# USBHUB.net
KiCad netlist of a schematic drawn in Altium Designer
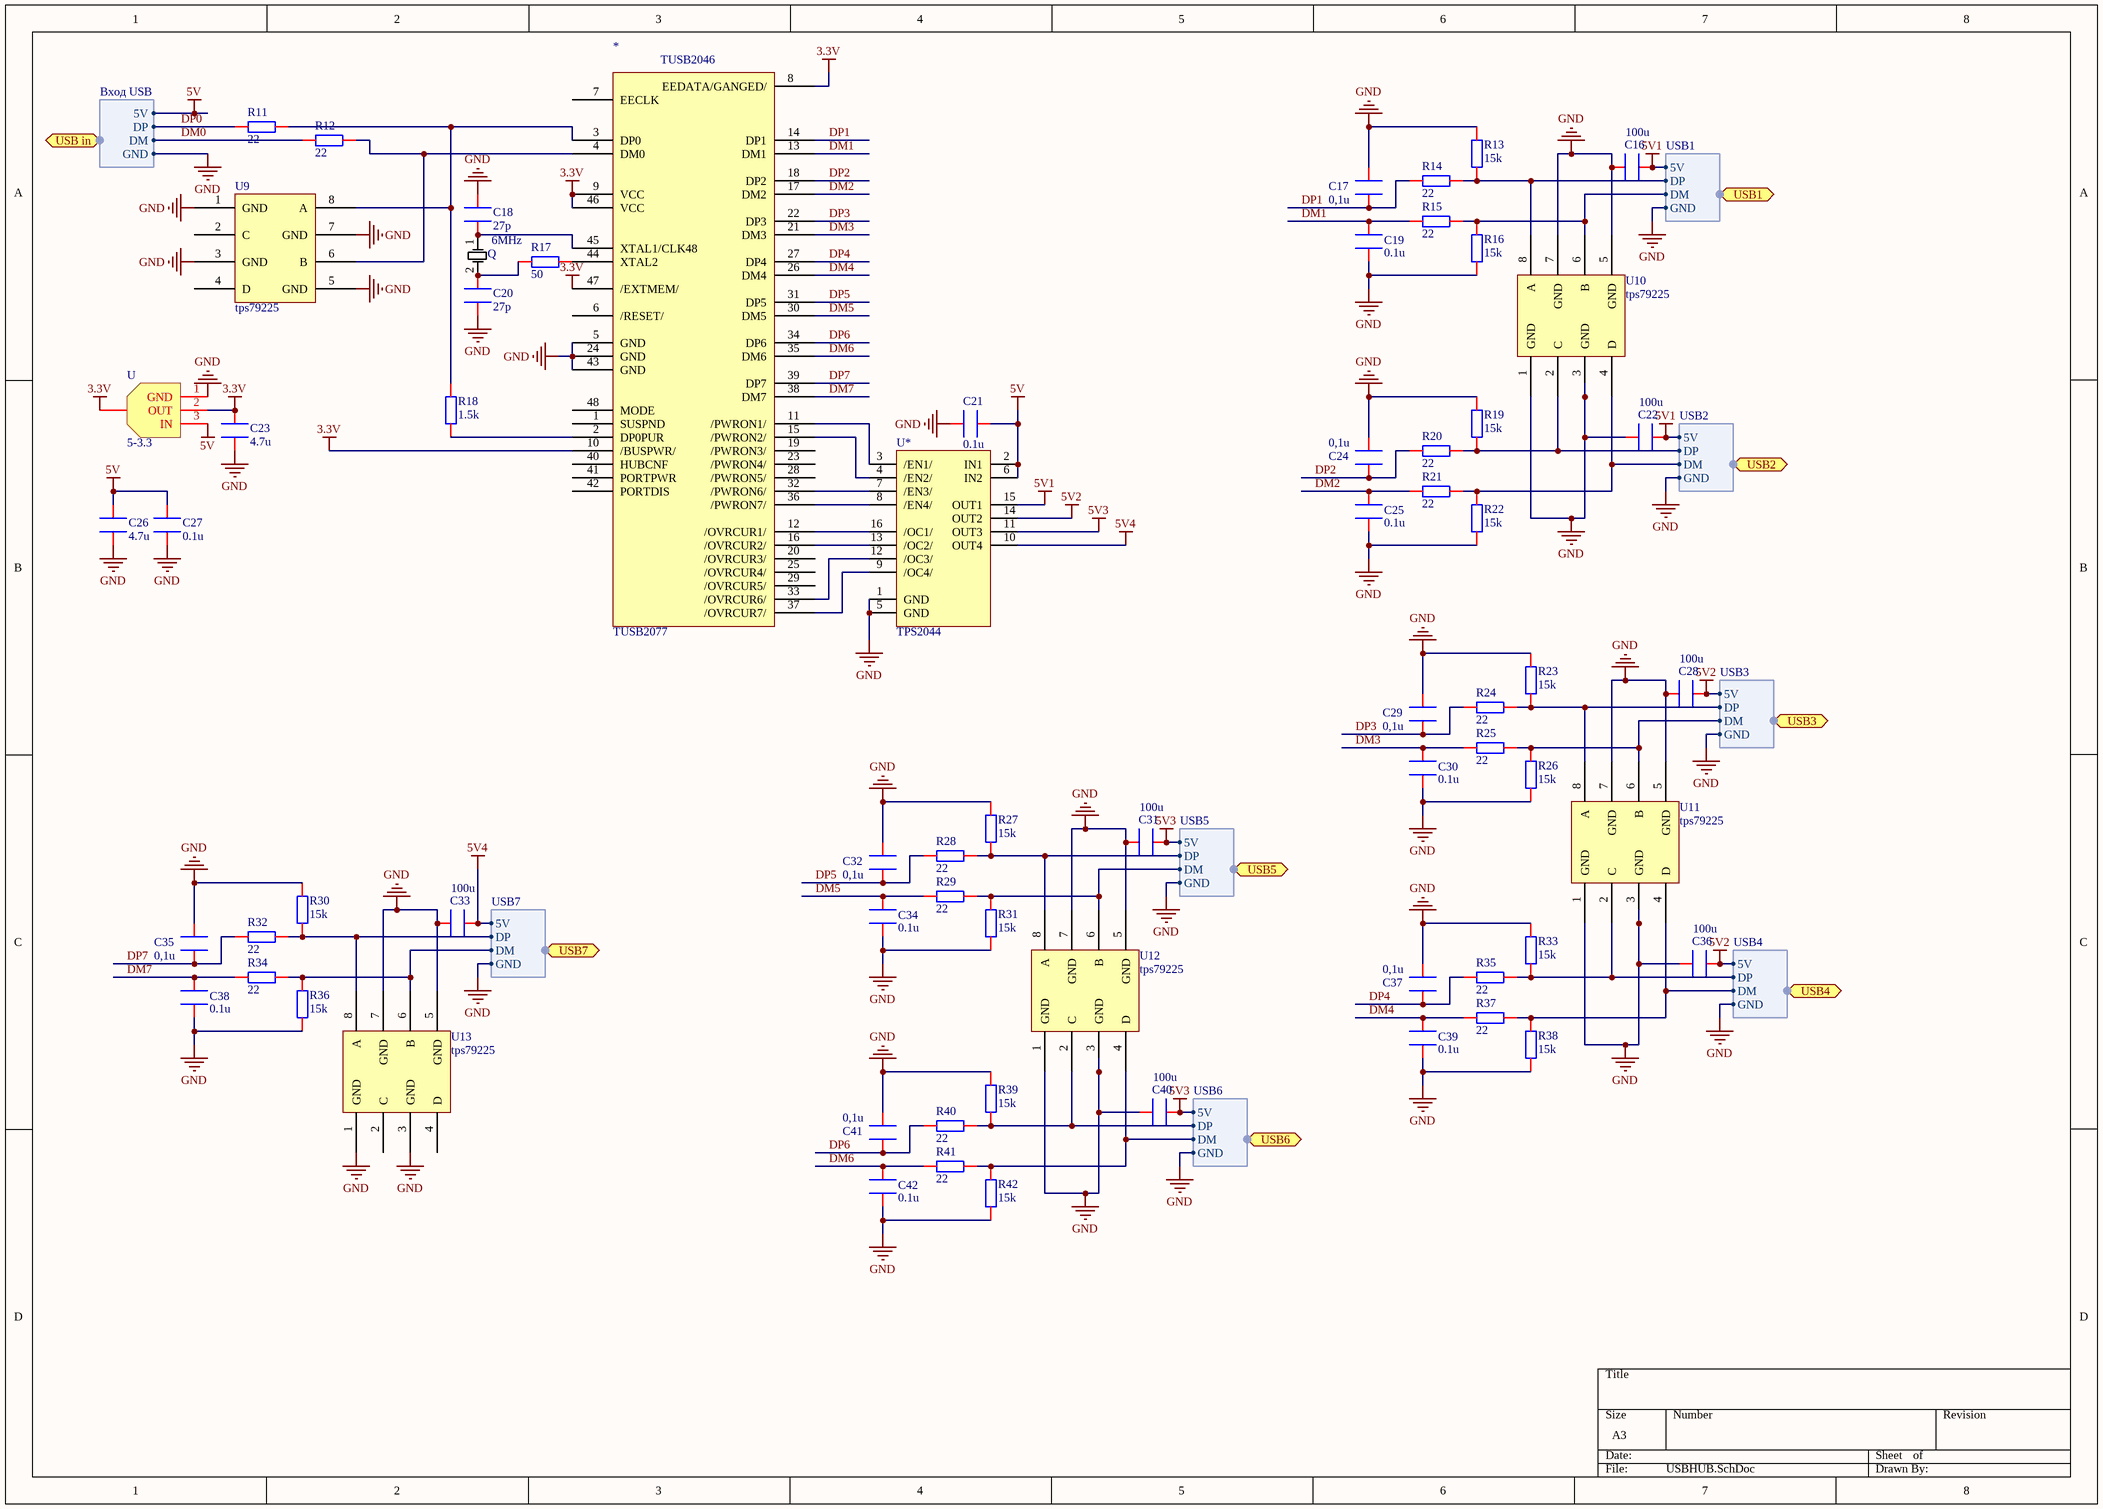
[diagram p0: USBHUB.SchDoc]

(export (version "E")
  (design (tool "Eeschema 10.0.6"))
  (components
    (comp (ref "*") (value "TUSB2077") (libsource (lib "Lib_001") (part "TUSB2077")))
    (comp (ref "C16") (value "100u") (footprint "SMD0603") (libsource (lib "Lib_001") (part "CAP")))
    (comp (ref "C17") (value "0,1u") (footprint "SMD0603") (libsource (lib "Lib_001") (part "CAP")))
    (comp (ref "C18") (value "27p") (footprint "SMD0603") (libsource (lib "Lib_001") (part "CAP")))
    (comp (ref "C19") (value "0.1u") (footprint "SMD0603") (libsource (lib "Lib_001") (part "CAP")))
    (comp (ref "C20") (value "27p") (footprint "SMD0603") (libsource (lib "Lib_001") (part "CAP")))
    (comp (ref "C21") (value "0.1u") (footprint "SMD0603") (libsource (lib "Lib_001") (part "CAP")))
    (comp (ref "C22") (value "100u") (footprint "SMD0603") (libsource (lib "Lib_001") (part "CAP")))
    (comp (ref "C23") (value "4.7u") (footprint "SMD0603") (libsource (lib "Lib_001") (part "CAP")))
    (comp (ref "C24") (value "0,1u") (footprint "SMD0603") (libsource (lib "Lib_001") (part "CAP")))
    (comp (ref "C25") (value "0.1u") (footprint "SMD0603") (libsource (lib "Lib_001") (part "CAP")))
    (comp (ref "C26") (value "4.7u") (footprint "SMD0603") (libsource (lib "Lib_001") (part "CAP")))
    (comp (ref "C27") (value "0.1u") (footprint "SMD0603") (libsource (lib "Lib_001") (part "CAP")))
    (comp (ref "C28") (value "100u") (footprint "SMD0603") (libsource (lib "Lib_001") (part "CAP")))
    (comp (ref "C29") (value "0,1u") (footprint "SMD0603") (libsource (lib "Lib_001") (part "CAP")))
    (comp (ref "C30") (value "0.1u") (footprint "SMD0603") (libsource (lib "Lib_001") (part "CAP")))
    (comp (ref "C31") (value "100u") (footprint "SMD0603") (libsource (lib "Lib_001") (part "CAP")))
    (comp (ref "C32") (value "0,1u") (footprint "SMD0603") (libsource (lib "Lib_001") (part "CAP")))
    (comp (ref "C33") (value "100u") (footprint "SMD0603") (libsource (lib "Lib_001") (part "CAP")))
    (comp (ref "C34") (value "0.1u") (footprint "SMD0603") (libsource (lib "Lib_001") (part "CAP")))
    (comp (ref "C35") (value "0,1u") (footprint "SMD0603") (libsource (lib "Lib_001") (part "CAP")))
    (comp (ref "C36") (value "100u") (footprint "SMD0603") (libsource (lib "Lib_001") (part "CAP")))
    (comp (ref "C37") (value "0,1u") (footprint "SMD0603") (libsource (lib "Lib_001") (part "CAP")))
    (comp (ref "C38") (value "0.1u") (footprint "SMD0603") (libsource (lib "Lib_001") (part "CAP")))
    (comp (ref "C39") (value "0.1u") (footprint "SMD0603") (libsource (lib "Lib_001") (part "CAP")))
    (comp (ref "C40") (value "100u") (footprint "SMD0603") (libsource (lib "Lib_001") (part "CAP")))
    (comp (ref "C41") (value "0,1u") (footprint "SMD0603") (libsource (lib "Lib_001") (part "CAP")))
    (comp (ref "C42") (value "0.1u") (footprint "SMD0603") (libsource (lib "Lib_001") (part "CAP")))
    (comp (ref "Q") (value "6MHz") (libsource (lib "Lib_001") (part "Quartz")))
    (comp (ref "R11") (value "22") (footprint "SMD0805") (libsource (lib "Lib_001") (part "RES_SMD")))
    (comp (ref "R12") (value "22") (footprint "SMD0805") (libsource (lib "Lib_001") (part "RES_SMD")))
    (comp (ref "R13") (value "15k") (footprint "SMD0805") (libsource (lib "Lib_001") (part "RES_SMD")))
    (comp (ref "R14") (value "22") (footprint "SMD0805") (libsource (lib "Lib_001") (part "RES_SMD")))
    (comp (ref "R15") (value "22") (footprint "SMD0805") (libsource (lib "Lib_001") (part "RES_SMD")))
    (comp (ref "R16") (value "15k") (footprint "SMD0805") (libsource (lib "Lib_001") (part "RES_SMD")))
    (comp (ref "R17") (value "50") (footprint "SMD0805") (libsource (lib "Lib_001") (part "RES_SMD")))
    (comp (ref "R18") (value "1.5k") (footprint "SMD0805") (libsource (lib "Lib_001") (part "RES_SMD")))
    (comp (ref "R19") (value "15k") (footprint "SMD0805") (libsource (lib "Lib_001") (part "RES_SMD")))
    (comp (ref "R20") (value "22") (footprint "SMD0805") (libsource (lib "Lib_001") (part "RES_SMD")))
    (comp (ref "R21") (value "22") (footprint "SMD0805") (libsource (lib "Lib_001") (part "RES_SMD")))
    (comp (ref "R22") (value "15k") (footprint "SMD0805") (libsource (lib "Lib_001") (part "RES_SMD")))
    (comp (ref "R23") (value "15k") (footprint "SMD0805") (libsource (lib "Lib_001") (part "RES_SMD")))
    (comp (ref "R24") (value "22") (footprint "SMD0805") (libsource (lib "Lib_001") (part "RES_SMD")))
    (comp (ref "R25") (value "22") (footprint "SMD0805") (libsource (lib "Lib_001") (part "RES_SMD")))
    (comp (ref "R26") (value "15k") (footprint "SMD0805") (libsource (lib "Lib_001") (part "RES_SMD")))
    (comp (ref "R27") (value "15k") (footprint "SMD0805") (libsource (lib "Lib_001") (part "RES_SMD")))
    (comp (ref "R28") (value "22") (footprint "SMD0805") (libsource (lib "Lib_001") (part "RES_SMD")))
    (comp (ref "R29") (value "22") (footprint "SMD0805") (libsource (lib "Lib_001") (part "RES_SMD")))
    (comp (ref "R30") (value "15k") (footprint "SMD0805") (libsource (lib "Lib_001") (part "RES_SMD")))
    (comp (ref "R31") (value "15k") (footprint "SMD0805") (libsource (lib "Lib_001") (part "RES_SMD")))
    (comp (ref "R32") (value "22") (footprint "SMD0805") (libsource (lib "Lib_001") (part "RES_SMD")))
    (comp (ref "R33") (value "15k") (footprint "SMD0805") (libsource (lib "Lib_001") (part "RES_SMD")))
    (comp (ref "R34") (value "22") (footprint "SMD0805") (libsource (lib "Lib_001") (part "RES_SMD")))
    (comp (ref "R35") (value "22") (footprint "SMD0805") (libsource (lib "Lib_001") (part "RES_SMD")))
    (comp (ref "R36") (value "15k") (footprint "SMD0805") (libsource (lib "Lib_001") (part "RES_SMD")))
    (comp (ref "R37") (value "22") (footprint "SMD0805") (libsource (lib "Lib_001") (part "RES_SMD")))
    (comp (ref "R38") (value "15k") (footprint "SMD0805") (libsource (lib "Lib_001") (part "RES_SMD")))
    (comp (ref "R39") (value "15k") (footprint "SMD0805") (libsource (lib "Lib_001") (part "RES_SMD")))
    (comp (ref "R40") (value "22") (footprint "SMD0805") (libsource (lib "Lib_001") (part "RES_SMD")))
    (comp (ref "R41") (value "22") (footprint "SMD0805") (libsource (lib "Lib_001") (part "RES_SMD")))
    (comp (ref "R42") (value "15k") (footprint "SMD0805") (libsource (lib "Lib_001") (part "RES_SMD")))
    (comp (ref "U") (value "5-3.3") (libsource (lib "Lib_001") (part "TLV1117LV")))
    (comp (ref "U*") (value "TPS2044") (footprint "VSSOP-8") (libsource (lib "Lib_001") (part "TPS2044")))
    (comp (ref "U9") (value "tps79225") (footprint "SOT-23-5") (libsource (lib "") (part "SN75240_1")))
    (comp (ref "U10") (value "tps79225") (footprint "SOT-23-5") (libsource (lib "Lib_001") (part "SN75240")))
    (comp (ref "U11") (value "tps79225") (footprint "SOT-23-5") (libsource (lib "Lib_001") (part "SN75240")))
    (comp (ref "U12") (value "tps79225") (footprint "SOT-23-5") (libsource (lib "Lib_001") (part "SN75240")))
    (comp (ref "U13") (value "tps79225") (footprint "SOT-23-5") (libsource (lib "Lib_001") (part "SN75240")))
  )
  (nets
    (net (code "10") (name "/DM0") (class "Default")
      (node (ref "R12") (pin "1") (pinfunction "1_1") (pintype "passive"))
    )
    (net (code "11") (name "/DM1") (class "Default")
      (node (ref "*") (pin "13") (pinfunction "DM1_13") (pintype "passive"))
      (node (ref "C19") (pin "1") (pinfunction "1_1") (pintype "passive"))
      (node (ref "R15") (pin "1") (pinfunction "1_1") (pintype "passive"))
    )
    (net (code "12") (name "/DM2") (class "Default")
      (node (ref "*") (pin "17") (pinfunction "DM2_17") (pintype "passive"))
      (node (ref "C25") (pin "1") (pinfunction "1_1") (pintype "passive"))
      (node (ref "R21") (pin "1") (pinfunction "1_1") (pintype "passive"))
    )
    (net (code "13") (name "/DM3") (class "Default")
      (node (ref "*") (pin "21") (pinfunction "DM3_21") (pintype "passive"))
      (node (ref "C30") (pin "1") (pinfunction "1_1") (pintype "passive"))
      (node (ref "R25") (pin "1") (pinfunction "1_1") (pintype "passive"))
    )
    (net (code "14") (name "/DM4") (class "Default")
      (node (ref "*") (pin "26") (pinfunction "DM4_26") (pintype "passive"))
      (node (ref "C39") (pin "1") (pinfunction "1_1") (pintype "passive"))
      (node (ref "R37") (pin "1") (pinfunction "1_1") (pintype "passive"))
    )
    (net (code "15") (name "/DM5") (class "Default")
      (node (ref "*") (pin "30") (pinfunction "DM5_30") (pintype "passive"))
      (node (ref "C34") (pin "1") (pinfunction "1_1") (pintype "passive"))
      (node (ref "R29") (pin "1") (pinfunction "1_1") (pintype "passive"))
    )
    (net (code "16") (name "/DM6") (class "Default")
      (node (ref "*") (pin "35") (pinfunction "DM6_35") (pintype "passive"))
      (node (ref "C42") (pin "1") (pinfunction "1_1") (pintype "passive"))
      (node (ref "R41") (pin "1") (pinfunction "1_1") (pintype "passive"))
    )
    (net (code "17") (name "/DM7") (class "Default")
      (node (ref "*") (pin "38") (pinfunction "DM7_38") (pintype "passive"))
      (node (ref "C38") (pin "1") (pinfunction "1_1") (pintype "passive"))
      (node (ref "R34") (pin "1") (pinfunction "1_1") (pintype "passive"))
    )
    (net (code "18") (name "/DP0") (class "Default")
      (node (ref "R11") (pin "1") (pinfunction "1_1") (pintype "passive"))
    )
    (net (code "19") (name "/DP1") (class "Default")
      (node (ref "*") (pin "14") (pinfunction "DP1_14") (pintype "passive"))
      (node (ref "C17") (pin "1") (pinfunction "1_1") (pintype "passive"))
      (node (ref "R14") (pin "1") (pinfunction "1_1") (pintype "passive"))
    )
    (net (code "20") (name "/DP2") (class "Default")
      (node (ref "*") (pin "18") (pinfunction "DP2_18") (pintype "passive"))
      (node (ref "C24") (pin "1") (pinfunction "1_1") (pintype "passive"))
      (node (ref "R20") (pin "1") (pinfunction "1_1") (pintype "passive"))
    )
    (net (code "21") (name "/DP3") (class "Default")
      (node (ref "*") (pin "22") (pinfunction "DP3_22") (pintype "passive"))
      (node (ref "C29") (pin "1") (pinfunction "1_1") (pintype "passive"))
      (node (ref "R24") (pin "1") (pinfunction "1_1") (pintype "passive"))
    )
    (net (code "22") (name "/DP4") (class "Default")
      (node (ref "*") (pin "27") (pinfunction "DP4_27") (pintype "passive"))
      (node (ref "C37") (pin "1") (pinfunction "1_1") (pintype "passive"))
      (node (ref "R35") (pin "1") (pinfunction "1_1") (pintype "passive"))
    )
    (net (code "23") (name "/DP5") (class "Default")
      (node (ref "*") (pin "31") (pinfunction "DP5_31") (pintype "passive"))
      (node (ref "C32") (pin "1") (pinfunction "1_1") (pintype "passive"))
      (node (ref "R28") (pin "1") (pinfunction "1_1") (pintype "passive"))
    )
    (net (code "24") (name "/DP6") (class "Default")
      (node (ref "*") (pin "34") (pinfunction "DP6_34") (pintype "passive"))
      (node (ref "C41") (pin "1") (pinfunction "1_1") (pintype "passive"))
      (node (ref "R40") (pin "1") (pinfunction "1_1") (pintype "passive"))
    )
    (net (code "25") (name "/DP7") (class "Default")
      (node (ref "*") (pin "39") (pinfunction "DP7_39") (pintype "passive"))
      (node (ref "C35") (pin "1") (pinfunction "1_1") (pintype "passive"))
      (node (ref "R32") (pin "1") (pinfunction "1_1") (pintype "passive"))
    )
    (net (code "34") (name "3.3V") (class "Default")
      (node (ref "*") (pin "10") (pinfunction "/BUSPWR/_10") (pintype "passive"))
      (node (ref "*") (pin "46") (pinfunction "VCC_46") (pintype "passive"))
      (node (ref "*") (pin "47") (pinfunction "/EXTMEM/_47") (pintype "passive"))
      (node (ref "*") (pin "8") (pinfunction "EEDATA/GANGED/_8") (pintype "passive"))
      (node (ref "*") (pin "9") (pinfunction "VCC_9") (pintype "passive"))
      (node (ref "C23") (pin "1") (pinfunction "1_1") (pintype "passive"))
      (node (ref "U") (pin "2") (pinfunction "OUT_2") (pintype "passive"))
      (node (ref "U") (pin "3") (pinfunction "OUT_3") (pintype "passive"))
    )
    (net (code "35") (name "5V") (class "Default")
      (node (ref "C21") (pin "1") (pinfunction "1_1") (pintype "passive"))
      (node (ref "C26") (pin "1") (pinfunction "1_1") (pintype "passive"))
      (node (ref "C27") (pin "1") (pinfunction "1_1") (pintype "passive"))
      (node (ref "U") (pin "3") (pinfunction "IN_3") (pintype "passive"))
      (node (ref "U*") (pin "2") (pinfunction "IN1_2") (pintype "passive"))
      (node (ref "U*") (pin "6") (pinfunction "IN2_6") (pintype "passive"))
    )
    (net (code "36") (name "5V1") (class "Default")
      (node (ref "C16") (pin "1") (pinfunction "1_1") (pintype "passive"))
      (node (ref "C22") (pin "1") (pinfunction "1_1") (pintype "passive"))
      (node (ref "U*") (pin "15") (pinfunction "OUT1_15") (pintype "passive"))
    )
    (net (code "37") (name "5V2") (class "Default")
      (node (ref "C28") (pin "1") (pinfunction "1_1") (pintype "passive"))
      (node (ref "C36") (pin "1") (pinfunction "1_1") (pintype "passive"))
      (node (ref "U*") (pin "14") (pinfunction "OUT2_14") (pintype "passive"))
    )
    (net (code "38") (name "5V3") (class "Default")
      (node (ref "C31") (pin "1") (pinfunction "1_1") (pintype "passive"))
      (node (ref "C40") (pin "1") (pinfunction "1_1") (pintype "passive"))
      (node (ref "U*") (pin "11") (pinfunction "OUT3_11") (pintype "passive"))
    )
    (net (code "39") (name "5V4") (class "Default")
      (node (ref "C33") (pin "1") (pinfunction "1_1") (pintype "passive"))
      (node (ref "U*") (pin "10") (pinfunction "OUT4_10") (pintype "passive"))
    )
    (net (code "40") (name "GND") (class "Default")
      (node (ref "*") (pin "24") (pinfunction "GND_24") (pintype "passive"))
      (node (ref "*") (pin "43") (pinfunction "GND_43") (pintype "passive"))
      (node (ref "*") (pin "5") (pinfunction "GND_5") (pintype "passive"))
      (node (ref "C16") (pin "2") (pinfunction "2_2") (pintype "passive"))
      (node (ref "C17") (pin "2") (pinfunction "2_2") (pintype "passive"))
      (node (ref "C18") (pin "1") (pinfunction "1_1") (pintype "passive"))
      (node (ref "C19") (pin "2") (pinfunction "2_2") (pintype "passive"))
      (node (ref "C20") (pin "2") (pinfunction "2_2") (pintype "passive"))
      (node (ref "C21") (pin "2") (pinfunction "2_2") (pintype "passive"))
      (node (ref "C22") (pin "2") (pinfunction "2_2") (pintype "passive"))
      (node (ref "C23") (pin "2") (pinfunction "2_2") (pintype "passive"))
      (node (ref "C24") (pin "2") (pinfunction "2_2") (pintype "passive"))
      (node (ref "C25") (pin "2") (pinfunction "2_2") (pintype "passive"))
      (node (ref "C26") (pin "2") (pinfunction "2_2") (pintype "passive"))
      (node (ref "C27") (pin "2") (pinfunction "2_2") (pintype "passive"))
      (node (ref "C28") (pin "2") (pinfunction "2_2") (pintype "passive"))
      (node (ref "C29") (pin "2") (pinfunction "2_2") (pintype "passive"))
      (node (ref "C30") (pin "2") (pinfunction "2_2") (pintype "passive"))
      (node (ref "C31") (pin "2") (pinfunction "2_2") (pintype "passive"))
      (node (ref "C32") (pin "2") (pinfunction "2_2") (pintype "passive"))
      (node (ref "C33") (pin "2") (pinfunction "2_2") (pintype "passive"))
      (node (ref "C34") (pin "2") (pinfunction "2_2") (pintype "passive"))
      (node (ref "C35") (pin "2") (pinfunction "2_2") (pintype "passive"))
      (node (ref "C36") (pin "2") (pinfunction "2_2") (pintype "passive"))
      (node (ref "C37") (pin "2") (pinfunction "2_2") (pintype "passive"))
      (node (ref "C38") (pin "2") (pinfunction "2_2") (pintype "passive"))
      (node (ref "C39") (pin "2") (pinfunction "2_2") (pintype "passive"))
      (node (ref "C40") (pin "2") (pinfunction "2_2") (pintype "passive"))
      (node (ref "C41") (pin "2") (pinfunction "2_2") (pintype "passive"))
      (node (ref "C42") (pin "2") (pinfunction "2_2") (pintype "passive"))
      (node (ref "R13") (pin "2") (pinfunction "2_2") (pintype "passive"))
      (node (ref "R16") (pin "1") (pinfunction "1_1") (pintype "passive"))
      (node (ref "R19") (pin "2") (pinfunction "2_2") (pintype "passive"))
      (node (ref "R22") (pin "1") (pinfunction "1_1") (pintype "passive"))
      (node (ref "R23") (pin "2") (pinfunction "2_2") (pintype "passive"))
      (node (ref "R26") (pin "1") (pinfunction "1_1") (pintype "passive"))
      (node (ref "R27") (pin "2") (pinfunction "2_2") (pintype "passive"))
      (node (ref "R30") (pin "2") (pinfunction "2_2") (pintype "passive"))
      (node (ref "R31") (pin "1") (pinfunction "1_1") (pintype "passive"))
      (node (ref "R33") (pin "2") (pinfunction "2_2") (pintype "passive"))
      (node (ref "R36") (pin "1") (pinfunction "1_1") (pintype "passive"))
      (node (ref "R38") (pin "1") (pinfunction "1_1") (pintype "passive"))
      (node (ref "R39") (pin "2") (pinfunction "2_2") (pintype "passive"))
      (node (ref "R42") (pin "1") (pinfunction "1_1") (pintype "passive"))
      (node (ref "U") (pin "1") (pinfunction "GND_1") (pintype "passive"))
      (node (ref "U*") (pin "1") (pinfunction "GND_1") (pintype "passive"))
      (node (ref "U*") (pin "5") (pinfunction "GND_5") (pintype "passive"))
      (node (ref "U10") (pin "1") (pinfunction "GND_1") (pintype "power_in"))
      (node (ref "U10") (pin "3") (pinfunction "GND_3") (pintype "passive"))
      (node (ref "U10") (pin "5") (pinfunction "GND_5") (pintype "power_in"))
      (node (ref "U10") (pin "7") (pinfunction "GND_7") (pintype "power_in"))
      (node (ref "U11") (pin "1") (pinfunction "GND_1") (pintype "power_in"))
      (node (ref "U11") (pin "3") (pinfunction "GND_3") (pintype "passive"))
      (node (ref "U11") (pin "5") (pinfunction "GND_5") (pintype "power_in"))
      (node (ref "U11") (pin "7") (pinfunction "GND_7") (pintype "power_in"))
      (node (ref "U12") (pin "1") (pinfunction "GND_1") (pintype "power_in"))
      (node (ref "U12") (pin "3") (pinfunction "GND_3") (pintype "passive"))
      (node (ref "U12") (pin "5") (pinfunction "GND_5") (pintype "power_in"))
      (node (ref "U12") (pin "7") (pinfunction "GND_7") (pintype "power_in"))
      (node (ref "U13") (pin "1") (pinfunction "GND_1") (pintype "power_in"))
      (node (ref "U13") (pin "3") (pinfunction "GND_3") (pintype "passive"))
      (node (ref "U13") (pin "5") (pinfunction "GND_5") (pintype "power_in"))
      (node (ref "U13") (pin "7") (pinfunction "GND_7") (pintype "power_in"))
      (node (ref "U9") (pin "1") (pinfunction "GND_1") (pintype "power_in"))
      (node (ref "U9") (pin "3") (pinfunction "GND_3") (pintype "passive"))
      (node (ref "U9") (pin "5") (pinfunction "GND_5") (pintype "power_in"))
      (node (ref "U9") (pin "7") (pinfunction "GND_7") (pintype "power_in"))
    )
    (net (code "41") (name "Net-(*-DM0)") (class "Default")
      (node (ref "*") (pin "4") (pinfunction "DM0_4") (pintype "passive"))
      (node (ref "R12") (pin "2") (pinfunction "2_2") (pintype "passive"))
      (node (ref "U9") (pin "6") (pinfunction "B_6") (pintype "passive"))
    )
    (net (code "42") (name "Net-(*-DP0)") (class "Default")
      (node (ref "*") (pin "3") (pinfunction "DP0_3") (pintype "passive"))
      (node (ref "R11") (pin "2") (pinfunction "2_2") (pintype "passive"))
      (node (ref "R18") (pin "2") (pinfunction "2_2") (pintype "passive"))
      (node (ref "U9") (pin "8") (pinfunction "A_8") (pintype "power_in"))
    )
    (net (code "43") (name "Net-(*-DP0PUR)") (class "Default")
      (node (ref "*") (pin "2") (pinfunction "DP0PUR_2") (pintype "passive"))
      (node (ref "R18") (pin "1") (pinfunction "1_1") (pintype "passive"))
    )
    (net (code "44") (name "Net-(*-XTAL1{slash}CLK48)") (class "Default")
      (node (ref "*") (pin "45") (pinfunction "XTAL1/CLK48_45") (pintype "passive"))
      (node (ref "C18") (pin "2") (pinfunction "2_2") (pintype "passive"))
      (node (ref "Q") (pin "1") (pinfunction "1_1") (pintype "passive"))
    )
    (net (code "45") (name "Net-(*-XTAL2)") (class "Default")
      (node (ref "*") (pin "44") (pinfunction "XTAL2_44") (pintype "passive"))
      (node (ref "R17") (pin "2") (pinfunction "2_2") (pintype "passive"))
    )
    (net (code "46") (name "Net-(*-{slash}OVRCUR1{slash})") (class "Default")
      (node (ref "*") (pin "12") (pinfunction "/OVRCUR1/_12") (pintype "passive"))
      (node (ref "U*") (pin "16") (pinfunction "/OC1/_16") (pintype "passive"))
    )
    (net (code "47") (name "Net-(*-{slash}OVRCUR2{slash})") (class "Default")
      (node (ref "*") (pin "16") (pinfunction "/OVRCUR2/_16") (pintype "passive"))
      (node (ref "U*") (pin "13") (pinfunction "/OC2/_13") (pintype "passive"))
    )
    (net (code "48") (name "Net-(*-{slash}OVRCUR6{slash})") (class "Default")
      (node (ref "*") (pin "33") (pinfunction "/OVRCUR6/_33") (pintype "passive"))
      (node (ref "U*") (pin "12") (pinfunction "/OC3/_12") (pintype "passive"))
    )
    (net (code "49") (name "Net-(*-{slash}OVRCUR7{slash})") (class "Default")
      (node (ref "*") (pin "37") (pinfunction "/OVRCUR7/_37") (pintype "passive"))
      (node (ref "U*") (pin "9") (pinfunction "/OC4/_9") (pintype "passive"))
    )
    (net (code "50") (name "Net-(*-{slash}PWRON1{slash})") (class "Default")
      (node (ref "*") (pin "11") (pinfunction "/PWRON1/_11") (pintype "passive"))
      (node (ref "U*") (pin "3") (pinfunction "/EN1/_3") (pintype "passive"))
    )
    (net (code "51") (name "Net-(*-{slash}PWRON2{slash})") (class "Default")
      (node (ref "*") (pin "15") (pinfunction "/PWRON2/_15") (pintype "passive"))
      (node (ref "U*") (pin "4") (pinfunction "/EN2/_4") (pintype "passive"))
    )
    (net (code "52") (name "Net-(*-{slash}PWRON6{slash})") (class "Default")
      (node (ref "*") (pin "32") (pinfunction "/PWRON6/_32") (pintype "passive"))
      (node (ref "U*") (pin "7") (pinfunction "/EN3/_7") (pintype "passive"))
    )
    (net (code "53") (name "Net-(*-{slash}PWRON7{slash})") (class "Default")
      (node (ref "*") (pin "36") (pinfunction "/PWRON7/_36") (pintype "passive"))
      (node (ref "U*") (pin "8") (pinfunction "/EN4/_8") (pintype "passive"))
    )
    (net (code "54") (name "Net-(C20-Pad1)") (class "Default")
      (node (ref "C20") (pin "1") (pinfunction "1_1") (pintype "passive"))
      (node (ref "Q") (pin "2") (pinfunction "2_2") (pintype "passive"))
      (node (ref "R17") (pin "1") (pinfunction "1_1") (pintype "passive"))
    )
    (net (code "55") (name "Net-(U10-A)") (class "Default")
      (node (ref "R13") (pin "1") (pinfunction "1_1") (pintype "passive"))
      (node (ref "R14") (pin "2") (pinfunction "2_2") (pintype "passive"))
      (node (ref "U10") (pin "8") (pinfunction "A_8") (pintype "power_in"))
    )
    (net (code "56") (name "Net-(U10-B)") (class "Default")
      (node (ref "R15") (pin "2") (pinfunction "2_2") (pintype "passive"))
      (node (ref "R16") (pin "2") (pinfunction "2_2") (pintype "passive"))
      (node (ref "U10") (pin "6") (pinfunction "B_6") (pintype "passive"))
    )
    (net (code "57") (name "Net-(U10-C)") (class "Default")
      (node (ref "R19") (pin "1") (pinfunction "1_1") (pintype "passive"))
      (node (ref "R20") (pin "2") (pinfunction "2_2") (pintype "passive"))
      (node (ref "U10") (pin "2") (pinfunction "C_2") (pintype "power_in"))
    )
    (net (code "58") (name "Net-(U10-D)") (class "Default")
      (node (ref "R21") (pin "2") (pinfunction "2_2") (pintype "passive"))
      (node (ref "R22") (pin "2") (pinfunction "2_2") (pintype "passive"))
      (node (ref "U10") (pin "4") (pinfunction "D_4") (pintype "power_in"))
    )
    (net (code "59") (name "Net-(U11-A)") (class "Default")
      (node (ref "R23") (pin "1") (pinfunction "1_1") (pintype "passive"))
      (node (ref "R24") (pin "2") (pinfunction "2_2") (pintype "passive"))
      (node (ref "U11") (pin "8") (pinfunction "A_8") (pintype "power_in"))
    )
    (net (code "60") (name "Net-(U11-B)") (class "Default")
      (node (ref "R25") (pin "2") (pinfunction "2_2") (pintype "passive"))
      (node (ref "R26") (pin "2") (pinfunction "2_2") (pintype "passive"))
      (node (ref "U11") (pin "6") (pinfunction "B_6") (pintype "passive"))
    )
    (net (code "61") (name "Net-(U11-C)") (class "Default")
      (node (ref "R33") (pin "1") (pinfunction "1_1") (pintype "passive"))
      (node (ref "R35") (pin "2") (pinfunction "2_2") (pintype "passive"))
      (node (ref "U11") (pin "2") (pinfunction "C_2") (pintype "power_in"))
    )
    (net (code "62") (name "Net-(U11-D)") (class "Default")
      (node (ref "R37") (pin "2") (pinfunction "2_2") (pintype "passive"))
      (node (ref "R38") (pin "2") (pinfunction "2_2") (pintype "passive"))
      (node (ref "U11") (pin "4") (pinfunction "D_4") (pintype "power_in"))
    )
    (net (code "63") (name "Net-(U12-A)") (class "Default")
      (node (ref "R27") (pin "1") (pinfunction "1_1") (pintype "passive"))
      (node (ref "R28") (pin "2") (pinfunction "2_2") (pintype "passive"))
      (node (ref "U12") (pin "8") (pinfunction "A_8") (pintype "power_in"))
    )
    (net (code "64") (name "Net-(U12-B)") (class "Default")
      (node (ref "R29") (pin "2") (pinfunction "2_2") (pintype "passive"))
      (node (ref "R31") (pin "2") (pinfunction "2_2") (pintype "passive"))
      (node (ref "U12") (pin "6") (pinfunction "B_6") (pintype "passive"))
    )
    (net (code "65") (name "Net-(U12-C)") (class "Default")
      (node (ref "R39") (pin "1") (pinfunction "1_1") (pintype "passive"))
      (node (ref "R40") (pin "2") (pinfunction "2_2") (pintype "passive"))
      (node (ref "U12") (pin "2") (pinfunction "C_2") (pintype "power_in"))
    )
    (net (code "66") (name "Net-(U12-D)") (class "Default")
      (node (ref "R41") (pin "2") (pinfunction "2_2") (pintype "passive"))
      (node (ref "R42") (pin "2") (pinfunction "2_2") (pintype "passive"))
      (node (ref "U12") (pin "4") (pinfunction "D_4") (pintype "power_in"))
    )
    (net (code "67") (name "Net-(U13-A)") (class "Default")
      (node (ref "R30") (pin "1") (pinfunction "1_1") (pintype "passive"))
      (node (ref "R32") (pin "2") (pinfunction "2_2") (pintype "passive"))
      (node (ref "U13") (pin "8") (pinfunction "A_8") (pintype "power_in"))
    )
    (net (code "68") (name "Net-(U13-B)") (class "Default")
      (node (ref "R34") (pin "2") (pinfunction "2_2") (pintype "passive"))
      (node (ref "R36") (pin "2") (pinfunction "2_2") (pintype "passive"))
      (node (ref "U13") (pin "6") (pinfunction "B_6") (pintype "passive"))
    )
    (net (code "69") (name "unconnected-(*-EECLK-Pad7)") (class "Default")
      (node (ref "*") (pin "7") (pinfunction "EECLK_7") (pintype "passive"))
    )
    (net (code "70") (name "unconnected-(*-HUBCNF-Pad40)") (class "Default")
      (node (ref "*") (pin "40") (pinfunction "HUBCNF_40") (pintype "passive"))
    )
    (net (code "71") (name "unconnected-(*-MODE-Pad48)") (class "Default")
      (node (ref "*") (pin "48") (pinfunction "MODE_48") (pintype "passive"))
    )
    (net (code "72") (name "unconnected-(*-PORTDIS-Pad42)") (class "Default")
      (node (ref "*") (pin "42") (pinfunction "PORTDIS_42") (pintype "passive"))
    )
    (net (code "73") (name "unconnected-(*-PORTPWR-Pad41)") (class "Default")
      (node (ref "*") (pin "41") (pinfunction "PORTPWR_41") (pintype "passive"))
    )
    (net (code "74") (name "unconnected-(*-SUSPND-Pad1)") (class "Default")
      (node (ref "*") (pin "1") (pinfunction "SUSPND_1") (pintype "passive"))
    )
    (net (code "75") (name "unconnected-(*-{slash}OVRCUR3{slash}-Pad20)") (class "Default")
      (node (ref "*") (pin "20") (pinfunction "/OVRCUR3/_20") (pintype "passive"))
    )
    (net (code "76") (name "unconnected-(*-{slash}OVRCUR4{slash}-Pad25)") (class "Default")
      (node (ref "*") (pin "25") (pinfunction "/OVRCUR4/_25") (pintype "passive"))
    )
    (net (code "77") (name "unconnected-(*-{slash}OVRCUR5{slash}-Pad29)") (class "Default")
      (node (ref "*") (pin "29") (pinfunction "/OVRCUR5/_29") (pintype "passive"))
    )
    (net (code "78") (name "unconnected-(*-{slash}PWRON3{slash}-Pad19)") (class "Default")
      (node (ref "*") (pin "19") (pinfunction "/PWRON3/_19") (pintype "passive"))
    )
    (net (code "79") (name "unconnected-(*-{slash}PWRON4{slash}-Pad23)") (class "Default")
      (node (ref "*") (pin "23") (pinfunction "/PWRON4/_23") (pintype "passive"))
    )
    (net (code "80") (name "unconnected-(*-{slash}PWRON5{slash}-Pad28)") (class "Default")
      (node (ref "*") (pin "28") (pinfunction "/PWRON5/_28") (pintype "passive"))
    )
    (net (code "81") (name "unconnected-(*-{slash}RESET{slash}-Pad6)") (class "Default")
      (node (ref "*") (pin "6") (pinfunction "/RESET/_6") (pintype "passive"))
    )
    (net (code "82") (name "unconnected-(U9-C-Pad2)") (class "Default")
      (node (ref "U9") (pin "2") (pinfunction "C_2") (pintype "power_in"))
    )
    (net (code "83") (name "unconnected-(U9-D-Pad4)") (class "Default")
      (node (ref "U9") (pin "4") (pinfunction "D_4") (pintype "power_in"))
    )
    (net (code "84") (name "unconnected-(U13-C-Pad2)") (class "Default")
      (node (ref "U13") (pin "2") (pinfunction "C_2") (pintype "power_in"))
    )
    (net (code "85") (name "unconnected-(U13-D-Pad4)") (class "Default")
      (node (ref "U13") (pin "4") (pinfunction "D_4") (pintype "power_in"))
    )
  )
)
